# eae-pld-x.net
KiCad netlist of a schematic drawn in EAGLE
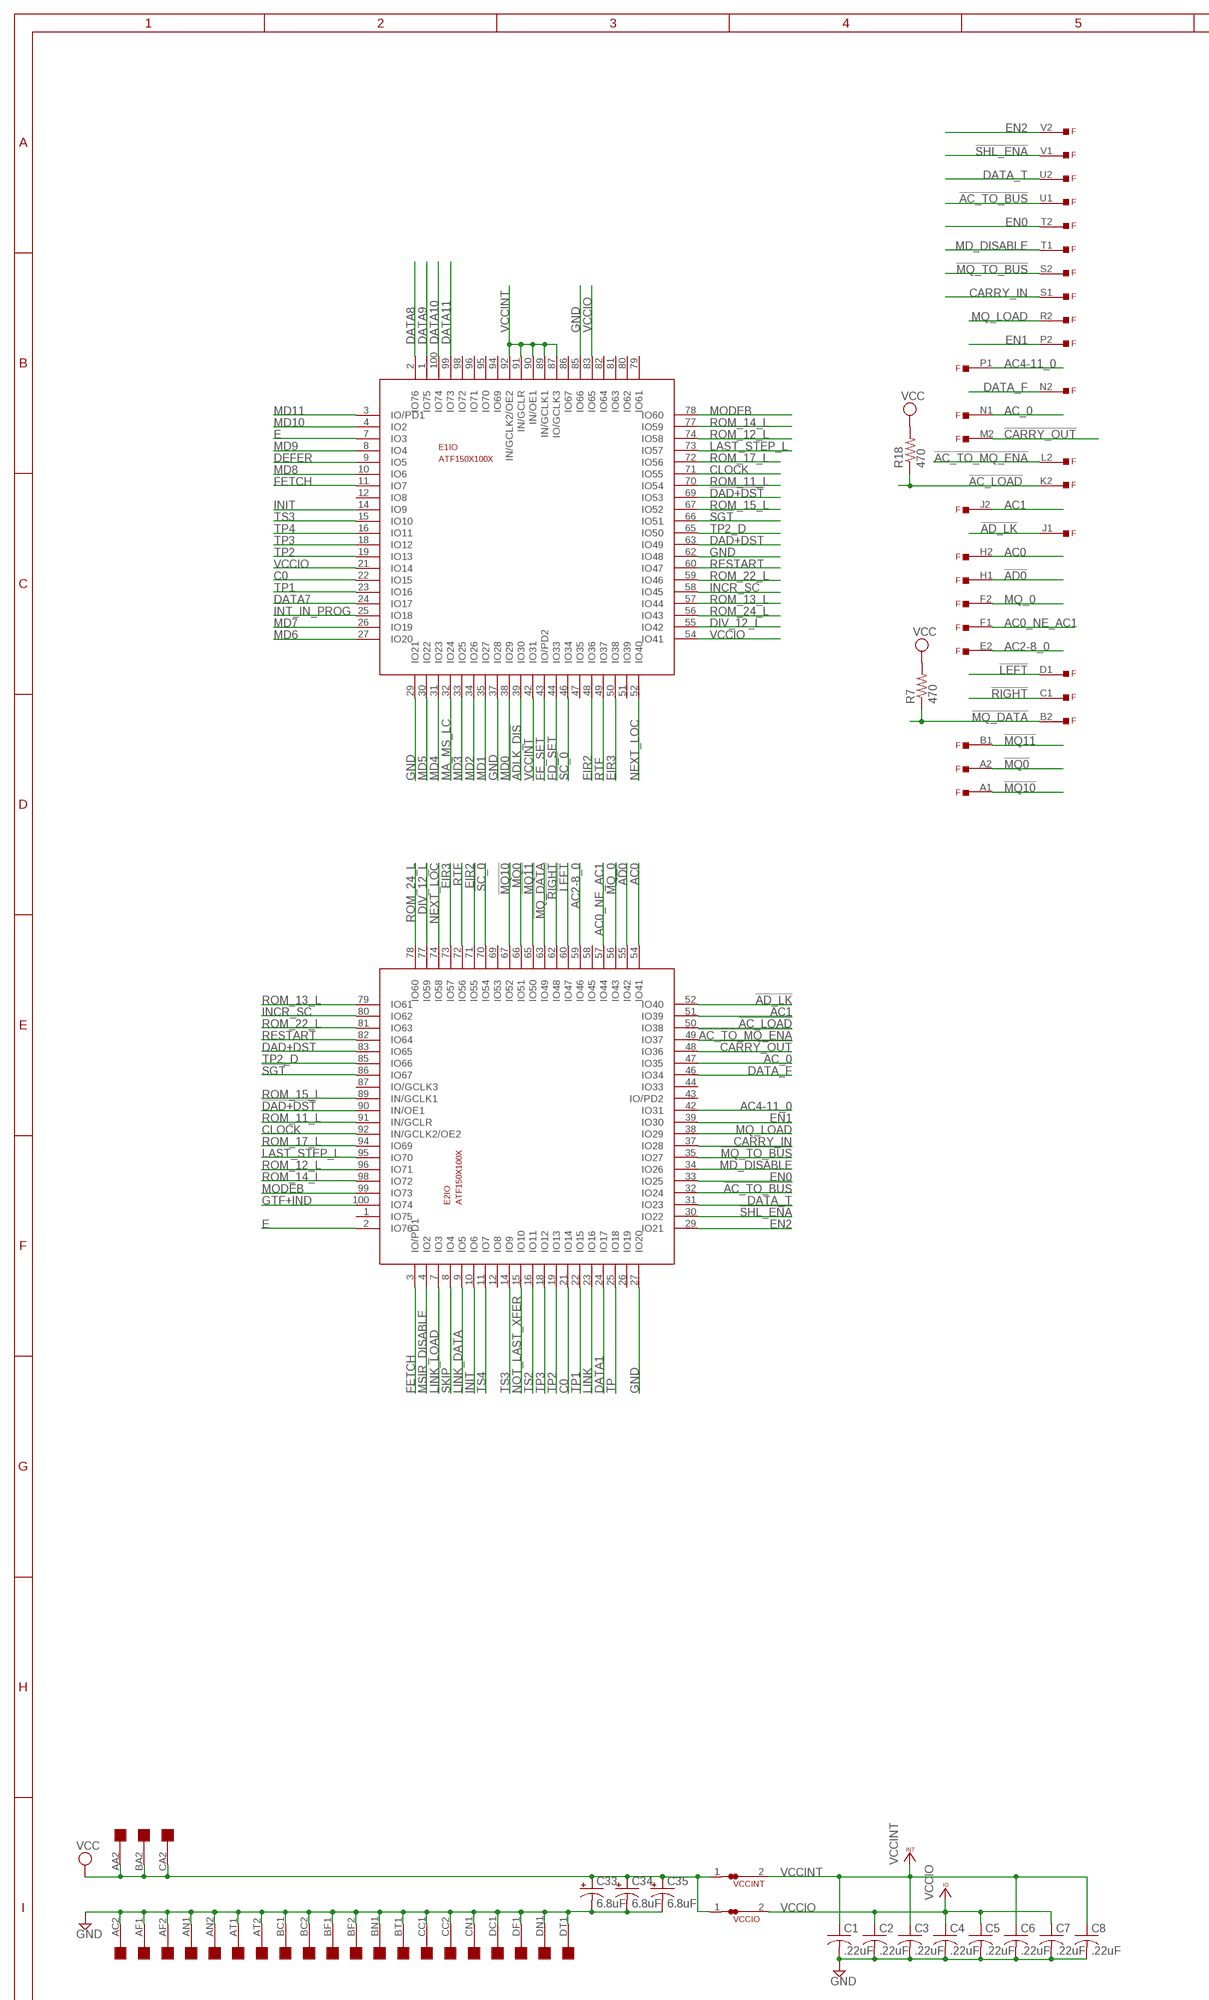
[diagram p0: schematic, sheet 1, part 1 of 2]
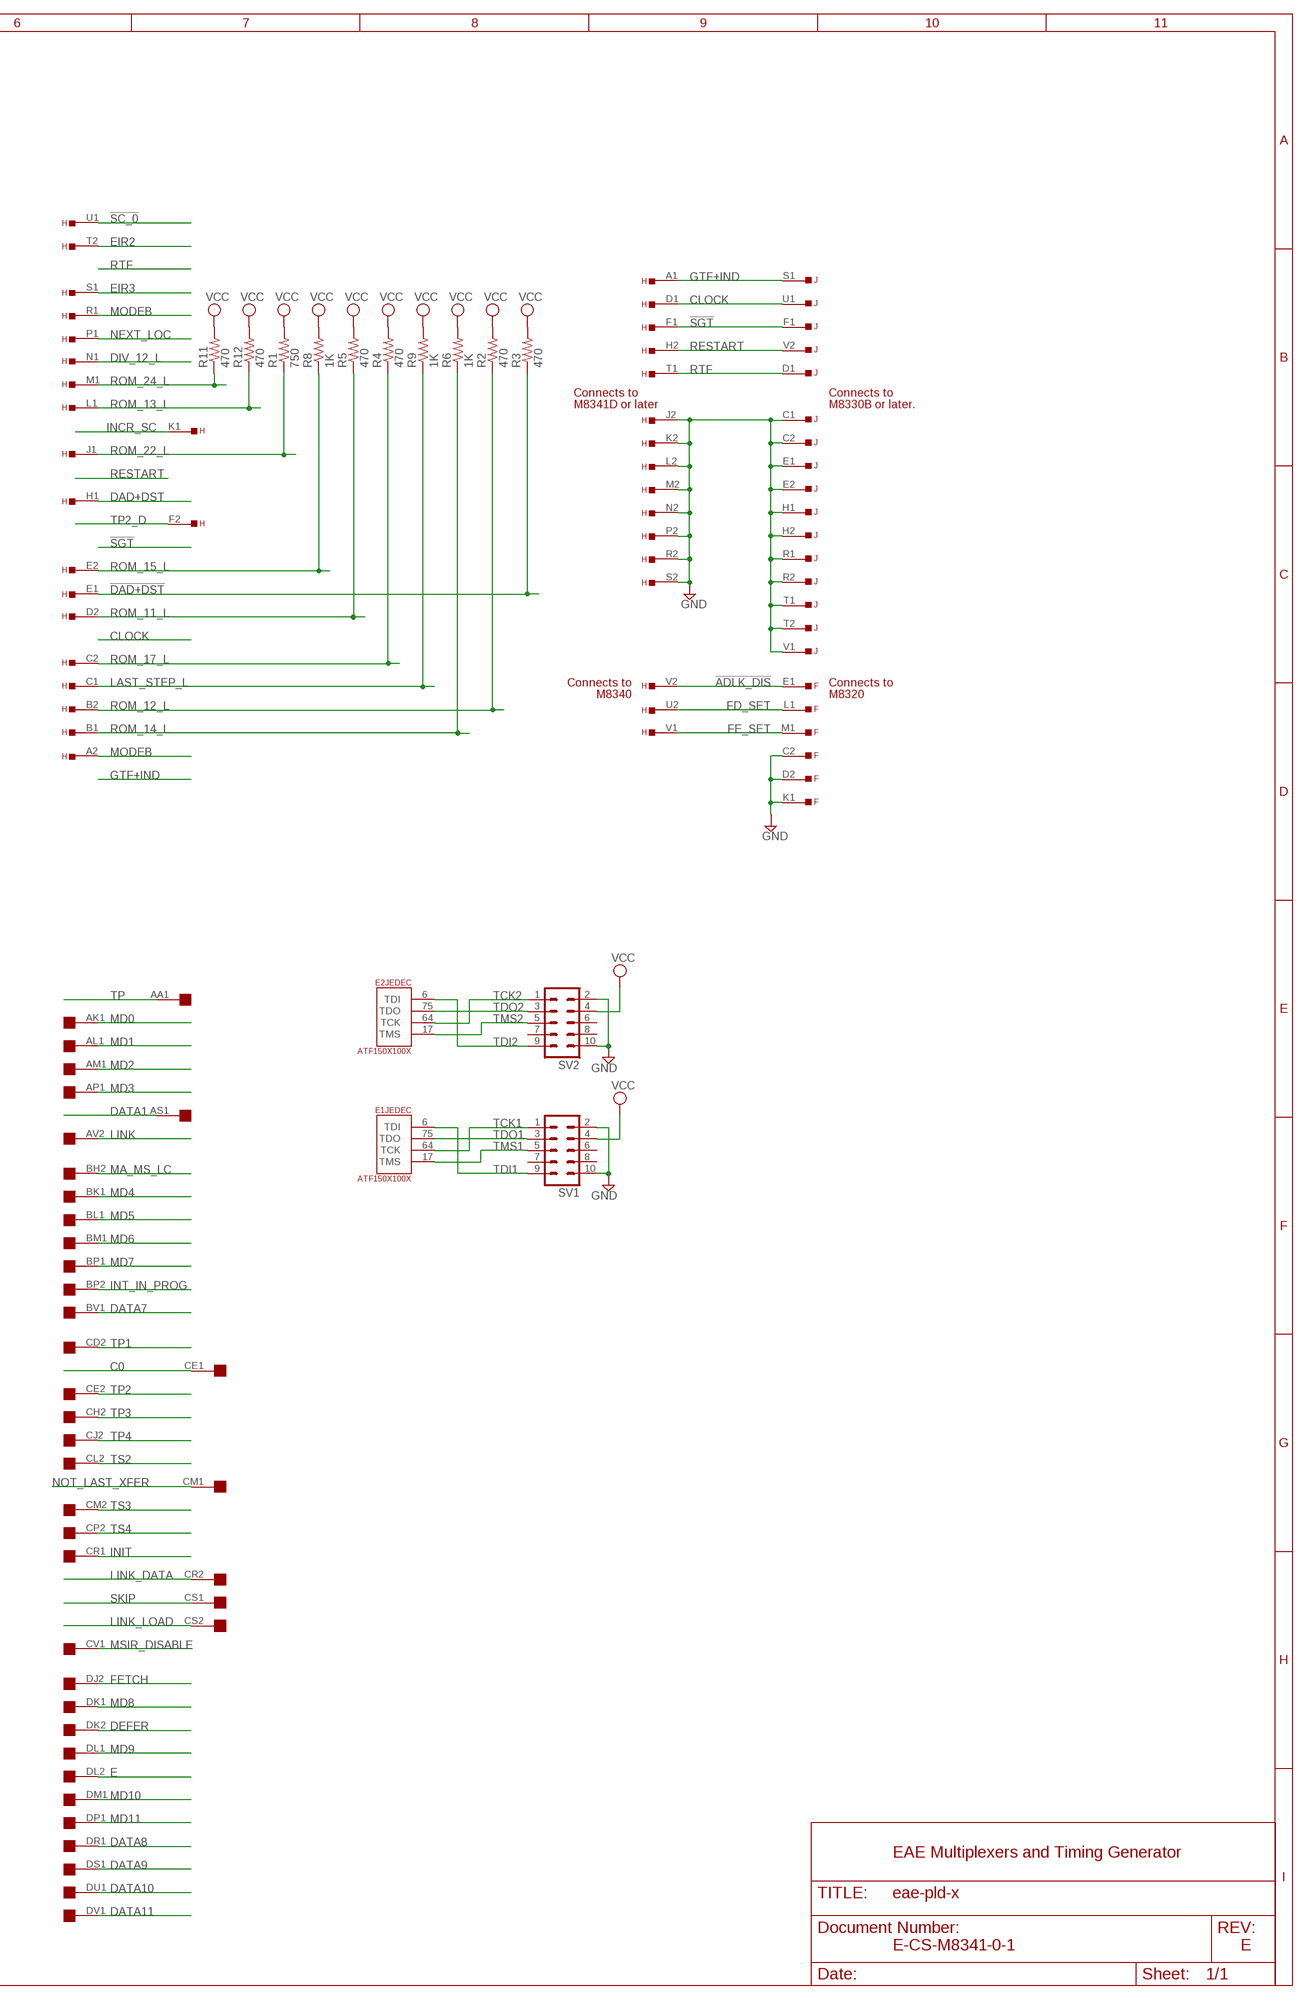
[diagram p1: schematic, sheet 1, part 2 of 2]

(export (version "E")
  (design (tool "Eeschema 10.0.6"))
  (components
    (comp (ref "C1")
      (value ".22uF")
      (footprint "eagle-import:C063-025X075")
      (libsource (lib "eagle-import") (part "C-US"))
    )
    (comp (ref "C2")
      (value ".22uF")
      (footprint "eagle-import:C063-025X075")
      (libsource (lib "eagle-import") (part "C-US"))
    )
    (comp (ref "C3")
      (value ".22uF")
      (footprint "eagle-import:C063-025X075")
      (libsource (lib "eagle-import") (part "C-US"))
    )
    (comp (ref "C4")
      (value ".22uF")
      (footprint "eagle-import:C063-025X075")
      (libsource (lib "eagle-import") (part "C-US"))
    )
    (comp (ref "C5")
      (value ".22uF")
      (footprint "eagle-import:C063-025X075")
      (libsource (lib "eagle-import") (part "C-US"))
    )
    (comp (ref "C6")
      (value ".22uF")
      (footprint "eagle-import:C063-025X075")
      (libsource (lib "eagle-import") (part "C-US"))
    )
    (comp (ref "C7")
      (value ".22uF")
      (footprint "eagle-import:C063-025X075")
      (libsource (lib "eagle-import") (part "C-US"))
    )
    (comp (ref "C8")
      (value ".22uF")
      (footprint "eagle-import:C063-025X075")
      (libsource (lib "eagle-import") (part "C-US"))
    )
    (comp (ref "C33")
      (value "6.8uF")
      (footprint "eagle-import:E12-8")
      (libsource (lib "eagle-import") (part "CPOL-USE20-8AXIAL"))
    )
    (comp (ref "C34")
      (value "6.8uF")
      (footprint "eagle-import:E12-8")
      (libsource (lib "eagle-import") (part "CPOL-USE20-8AXIAL"))
    )
    (comp (ref "C35")
      (value "6.8uF")
      (footprint "eagle-import:E12-8")
      (libsource (lib "eagle-import") (part "CPOL-USE20-8AXIAL"))
    )
    (comp (ref "E1")
      (value "ATF150X100X")
      (footprint "eagle-import:TH100B")
      (libsource (lib "eagle-import") (part "ATF150X100X"))
    )
    (comp (ref "E2")
      (value "ATF150X100X")
      (footprint "eagle-import:TH100B")
      (libsource (lib "eagle-import") (part "ATF150X100X"))
    )
    (comp (ref "F")
      (value "EDGE-TOP")
      (footprint "eagle-import:EDGE-CON2")
      (libsource (lib "eagle-import") (part "EDGE-TOP"))
    )
    (comp (ref "H")
      (value "EDGE-TOP")
      (footprint "eagle-import:EDGE-CON2")
      (libsource (lib "eagle-import") (part "EDGE-TOP"))
    )
    (comp (ref "J")
      (value "EDGE-TOP")
      (footprint "eagle-import:EDGE-CON2")
      (libsource (lib "eagle-import") (part "EDGE-TOP"))
    )
    (comp (ref "R1")
      (value "750")
      (footprint "eagle-import:0207_10")
      (libsource (lib "eagle-import") (part "R-US_0207/10"))
    )
    (comp (ref "R2")
      (value "470")
      (footprint "eagle-import:0207_10")
      (libsource (lib "eagle-import") (part "R-US_0207/10"))
    )
    (comp (ref "R3")
      (value "470")
      (footprint "eagle-import:0207_10")
      (libsource (lib "eagle-import") (part "R-US_0207/10"))
    )
    (comp (ref "R4")
      (value "470")
      (footprint "eagle-import:0207_10")
      (libsource (lib "eagle-import") (part "R-US_0207/10"))
    )
    (comp (ref "R5")
      (value "470")
      (footprint "eagle-import:0207_10")
      (libsource (lib "eagle-import") (part "R-US_0207/10"))
    )
    (comp (ref "R6")
      (value "1K")
      (footprint "eagle-import:0207_10")
      (libsource (lib "eagle-import") (part "R-US_0207/10"))
    )
    (comp (ref "R7")
      (value "470")
      (footprint "eagle-import:0207_10")
      (libsource (lib "eagle-import") (part "R-US_0207/10"))
    )
    (comp (ref "R8")
      (value "1K")
      (footprint "eagle-import:0207_10")
      (libsource (lib "eagle-import") (part "R-US_0207/10"))
    )
    (comp (ref "R9")
      (value "1K")
      (footprint "eagle-import:0207_10")
      (libsource (lib "eagle-import") (part "R-US_0207/10"))
    )
    (comp (ref "R11")
      (value "470")
      (footprint "eagle-import:0207_10")
      (libsource (lib "eagle-import") (part "R-US_0207/10"))
    )
    (comp (ref "R12")
      (value "470")
      (footprint "eagle-import:0207_10")
      (libsource (lib "eagle-import") (part "R-US_0207/10"))
    )
    (comp (ref "R18")
      (value "470")
      (footprint "eagle-import:0207_10")
      (libsource (lib "eagle-import") (part "R-US_0207/10"))
    )
    (comp (ref "SV1")
      (value "ML10")
      (footprint "eagle-import:ML10")
      (libsource (lib "eagle-import") (part "ML10"))
    )
    (comp (ref "SV2")
      (value "ML10")
      (footprint "eagle-import:ML10")
      (libsource (lib "eagle-import") (part "ML10"))
    )
    (comp (ref "U$1")
      (value "QUAD")
      (footprint "eagle-import:EDGE-CON8")
      (libsource (lib "eagle-import") (part "QUAD"))
    )
    (comp (ref "VCCINT")
      (value "JUMPER-NC1")
      (footprint "eagle-import:NC1")
      (libsource (lib "eagle-import") (part "JUMPER-NC1"))
    )
    (comp (ref "VCCIO")
      (value "JUMPER-NC1")
      (footprint "eagle-import:NC1")
      (libsource (lib "eagle-import") (part "JUMPER-NC1"))
    )
  )
  (nets
    (net (code "1") (name "/AC0") (class "Default")
      (node (ref "E2") (pin "54") (pinfunction "IO41_54") (pintype "bidirectional"))
      (node (ref "F") (pin "H2") (pinfunction "P_H2") (pintype "passive"))
    )
    (net (code "2") (name "/AC0_NE_AC1") (class "Default")
      (node (ref "E2") (pin "57") (pinfunction "IO44_57") (pintype "bidirectional"))
      (node (ref "F") (pin "F1") (pinfunction "P_F1") (pintype "passive"))
    )
    (net (code "3") (name "/AC1") (class "Default")
      (node (ref "E2") (pin "51") (pinfunction "IO39_51") (pintype "bidirectional"))
      (node (ref "F") (pin "J2") (pinfunction "P_J2") (pintype "passive"))
    )
    (net (code "4") (name "/AC2-8_0") (class "Default")
      (node (ref "E2") (pin "59") (pinfunction "IO46_59") (pintype "bidirectional"))
      (node (ref "F") (pin "E2") (pinfunction "P_E2") (pintype "passive"))
    )
    (net (code "5") (name "/AC4-11_0") (class "Default")
      (node (ref "E2") (pin "42") (pinfunction "IO31_42") (pintype "bidirectional"))
      (node (ref "F") (pin "P1") (pinfunction "P_P1") (pintype "passive"))
    )
    (net (code "6") (name "/AC_0") (class "Default")
      (node (ref "E2") (pin "47") (pinfunction "IO35_47") (pintype "bidirectional"))
      (node (ref "F") (pin "N1") (pinfunction "P_N1") (pintype "passive"))
    )
    (net (code "7") (name "/C0") (class "Default")
      (node (ref "E1") (pin "22") (pinfunction "IO15_22") (pintype "bidirectional"))
      (node (ref "E2") (pin "21") (pinfunction "IO14_21") (pintype "bidirectional"))
      (node (ref "U$1") (pin "CE1") (pinfunction "1_CE1") (pintype "bidirectional"))
    )
    (net (code "8") (name "/CARRY_IN") (class "Default")
      (node (ref "E2") (pin "37") (pinfunction "IO28_37") (pintype "bidirectional"))
      (node (ref "F") (pin "S1") (pinfunction "P_S1") (pintype "passive"))
    )
    (net (code "9") (name "/CLOCK") (class "Default")
      (node (ref "E1") (pin "71") (pinfunction "IO55_71") (pintype "bidirectional"))
      (node (ref "E2") (pin "92") (pinfunction "IN/GCLK2/OE2_92") (pintype "input"))
      (node (ref "H") (pin "D1") (pinfunction "P_D1") (pintype "passive"))
      (node (ref "J") (pin "U1") (pinfunction "P_U1") (pintype "passive"))
    )
    (net (code "10") (name "/DAD+DST") (class "Default")
      (node (ref "E1") (pin "63") (pinfunction "IO49_63") (pintype "bidirectional"))
      (node (ref "E2") (pin "83") (pinfunction "IO65_83") (pintype "bidirectional"))
      (node (ref "H") (pin "H1") (pinfunction "P_H1") (pintype "passive"))
    )
    (net (code "11") (name "/DATA1") (class "Default")
      (node (ref "E2") (pin "24") (pinfunction "IO17_24") (pintype "bidirectional"))
      (node (ref "U$1") (pin "AS1") (pinfunction "1_AS1") (pintype "bidirectional"))
    )
    (net (code "12") (name "/DATA7") (class "Default")
      (node (ref "E1") (pin "24") (pinfunction "IO17_24") (pintype "bidirectional"))
      (node (ref "U$1") (pin "BV1") (pinfunction "1_BV1") (pintype "bidirectional"))
    )
    (net (code "13") (name "/DATA8") (class "Default")
      (node (ref "E1") (pin "2") (pinfunction "IO76_2") (pintype "bidirectional"))
      (node (ref "U$1") (pin "DR1") (pinfunction "1_DR1") (pintype "bidirectional"))
    )
    (net (code "14") (name "/DATA9") (class "Default")
      (node (ref "E1") (pin "1") (pinfunction "IO75_1") (pintype "bidirectional"))
      (node (ref "U$1") (pin "DS1") (pinfunction "1_DS1") (pintype "bidirectional"))
    )
    (net (code "15") (name "/DATA10") (class "Default")
      (node (ref "E1") (pin "100") (pinfunction "IO74_100") (pintype "bidirectional"))
      (node (ref "U$1") (pin "DU1") (pinfunction "1_DU1") (pintype "bidirectional"))
    )
    (net (code "16") (name "/DATA11") (class "Default")
      (node (ref "E1") (pin "99") (pinfunction "IO73_99") (pintype "bidirectional"))
      (node (ref "U$1") (pin "DV1") (pinfunction "1_DV1") (pintype "bidirectional"))
    )
    (net (code "17") (name "/DATA_F") (class "Default")
      (node (ref "E2") (pin "46") (pinfunction "IO34_46") (pintype "bidirectional"))
      (node (ref "F") (pin "N2") (pinfunction "P_N2") (pintype "passive"))
    )
    (net (code "18") (name "/DATA_T") (class "Default")
      (node (ref "E2") (pin "31") (pinfunction "IO23_31") (pintype "bidirectional"))
      (node (ref "F") (pin "U2") (pinfunction "P_U2") (pintype "passive"))
    )
    (net (code "19") (name "/DEFER") (class "Default")
      (node (ref "E1") (pin "9") (pinfunction "IO5_9") (pintype "bidirectional"))
      (node (ref "U$1") (pin "DK2") (pinfunction "1_DK2") (pintype "bidirectional"))
    )
    (net (code "20") (name "/DIV_12_L") (class "Default")
      (node (ref "E1") (pin "55") (pinfunction "IO42_55") (pintype "bidirectional"))
      (node (ref "E2") (pin "77") (pinfunction "IO59_77") (pintype "bidirectional"))
      (node (ref "H") (pin "N1") (pinfunction "P_N1") (pintype "passive"))
    )
    (net (code "21") (name "/E") (class "Default")
      (node (ref "E1") (pin "7") (pinfunction "IO3_7") (pintype "bidirectional"))
      (node (ref "E2") (pin "2") (pinfunction "IO76_2") (pintype "bidirectional"))
      (node (ref "U$1") (pin "DL2") (pinfunction "1_DL2") (pintype "bidirectional"))
    )
    (net (code "22") (name "/EIR2") (class "Default")
      (node (ref "E1") (pin "48") (pinfunction "IO36_48") (pintype "bidirectional"))
      (node (ref "E2") (pin "71") (pinfunction "IO55_71") (pintype "bidirectional"))
      (node (ref "H") (pin "T2") (pinfunction "P_T2") (pintype "passive"))
    )
    (net (code "23") (name "/EIR3") (class "Default")
      (node (ref "E1") (pin "50") (pinfunction "IO38_50") (pintype "bidirectional"))
      (node (ref "E2") (pin "73") (pinfunction "IO57_73") (pintype "bidirectional"))
      (node (ref "H") (pin "S1") (pinfunction "P_S1") (pintype "passive"))
    )
    (net (code "24") (name "/EN0") (class "Default")
      (node (ref "E2") (pin "33") (pinfunction "IO25_33") (pintype "bidirectional"))
      (node (ref "F") (pin "T2") (pinfunction "P_T2") (pintype "passive"))
    )
    (net (code "25") (name "/EN1") (class "Default")
      (node (ref "E2") (pin "39") (pinfunction "IO30_39") (pintype "bidirectional"))
      (node (ref "F") (pin "P2") (pinfunction "P_P2") (pintype "passive"))
    )
    (net (code "26") (name "/EN2") (class "Default")
      (node (ref "E2") (pin "29") (pinfunction "IO21_29") (pintype "bidirectional"))
      (node (ref "F") (pin "V2") (pinfunction "P_V2") (pintype "passive"))
    )
    (net (code "27") (name "/FD_SET") (class "Default")
      (node (ref "E1") (pin "44") (pinfunction "IO33_44") (pintype "bidirectional"))
      (node (ref "F") (pin "L1") (pinfunction "P_L1") (pintype "passive"))
      (node (ref "H") (pin "U2") (pinfunction "P_U2") (pintype "passive"))
    )
    (net (code "28") (name "/FETCH") (class "Default")
      (node (ref "E1") (pin "11") (pinfunction "IO7_11") (pintype "bidirectional"))
      (node (ref "E2") (pin "3") (pinfunction "IO/PD1_3") (pintype "bidirectional"))
      (node (ref "U$1") (pin "DJ2") (pinfunction "1_DJ2") (pintype "bidirectional"))
    )
    (net (code "29") (name "/FE_SET") (class "Default")
      (node (ref "E1") (pin "43") (pinfunction "IO/PD2_43") (pintype "bidirectional"))
      (node (ref "F") (pin "M1") (pinfunction "P_M1") (pintype "passive"))
      (node (ref "H") (pin "V1") (pinfunction "P_V1") (pintype "passive"))
    )
    (net (code "30") (name "/GTF+IND") (class "Default")
      (node (ref "E2") (pin "100") (pinfunction "IO74_100") (pintype "bidirectional"))
      (node (ref "H") (pin "A1") (pinfunction "P_A1") (pintype "passive"))
      (node (ref "J") (pin "S1") (pinfunction "P_S1") (pintype "passive"))
    )
    (net (code "31") (name "/INCR_SC") (class "Default")
      (node (ref "E1") (pin "58") (pinfunction "IO45_58") (pintype "bidirectional"))
      (node (ref "E2") (pin "80") (pinfunction "IO62_80") (pintype "bidirectional"))
      (node (ref "H") (pin "K1") (pinfunction "P_K1") (pintype "passive"))
    )
    (net (code "32") (name "/INIT") (class "Default")
      (node (ref "E1") (pin "14") (pinfunction "IO9_14") (pintype "bidirectional"))
      (node (ref "E2") (pin "10") (pinfunction "IO6_10") (pintype "bidirectional"))
      (node (ref "U$1") (pin "CR1") (pinfunction "1_CR1") (pintype "bidirectional"))
    )
    (net (code "33") (name "/INT_IN_PROG") (class "Default")
      (node (ref "E1") (pin "25") (pinfunction "IO18_25") (pintype "bidirectional"))
      (node (ref "U$1") (pin "BP2") (pinfunction "1_BP2") (pintype "bidirectional"))
    )
    (net (code "34") (name "/LAST_STEP_L") (class "Default")
      (node (ref "E1") (pin "73") (pinfunction "IO57_73") (pintype "bidirectional"))
      (node (ref "E2") (pin "95") (pinfunction "IO70_95") (pintype "bidirectional"))
      (node (ref "H") (pin "C1") (pinfunction "P_C1") (pintype "passive"))
      (node (ref "R9") (pin "1") (pinfunction "1_1") (pintype "passive"))
    )
    (net (code "35") (name "/LINK") (class "Default")
      (node (ref "E2") (pin "23") (pinfunction "IO16_23") (pintype "bidirectional"))
      (node (ref "U$1") (pin "AV2") (pinfunction "1_AV2") (pintype "bidirectional"))
    )
    (net (code "36") (name "/LINK_DATA") (class "Default")
      (node (ref "E2") (pin "9") (pinfunction "IO5_9") (pintype "bidirectional"))
      (node (ref "U$1") (pin "CR2") (pinfunction "1_CR2") (pintype "bidirectional"))
    )
    (net (code "37") (name "/LINK_LOAD") (class "Default")
      (node (ref "E2") (pin "7") (pinfunction "IO3_7") (pintype "bidirectional"))
      (node (ref "U$1") (pin "CS2") (pinfunction "1_CS2") (pintype "bidirectional"))
    )
    (net (code "38") (name "/MA_MS_LC") (class "Default")
      (node (ref "E1") (pin "32") (pinfunction "IO24_32") (pintype "bidirectional"))
      (node (ref "U$1") (pin "BH2") (pinfunction "1_BH2") (pintype "bidirectional"))
    )
    (net (code "39") (name "/MD0") (class "Default")
      (node (ref "E1") (pin "38") (pinfunction "IO29_38") (pintype "bidirectional"))
      (node (ref "U$1") (pin "AK1") (pinfunction "1_AK1") (pintype "bidirectional"))
    )
    (net (code "40") (name "/MD1") (class "Default")
      (node (ref "E1") (pin "35") (pinfunction "IO27_35") (pintype "bidirectional"))
      (node (ref "U$1") (pin "AL1") (pinfunction "1_AL1") (pintype "bidirectional"))
    )
    (net (code "41") (name "/MD2") (class "Default")
      (node (ref "E1") (pin "34") (pinfunction "IO26_34") (pintype "bidirectional"))
      (node (ref "U$1") (pin "AM1") (pinfunction "1_AM1") (pintype "bidirectional"))
    )
    (net (code "42") (name "/MD3") (class "Default")
      (node (ref "E1") (pin "33") (pinfunction "IO25_33") (pintype "bidirectional"))
      (node (ref "U$1") (pin "AP1") (pinfunction "1_AP1") (pintype "bidirectional"))
    )
    (net (code "43") (name "/MD4") (class "Default")
      (node (ref "E1") (pin "31") (pinfunction "IO23_31") (pintype "bidirectional"))
      (node (ref "U$1") (pin "BK1") (pinfunction "1_BK1") (pintype "bidirectional"))
    )
    (net (code "44") (name "/MD5") (class "Default")
      (node (ref "E1") (pin "30") (pinfunction "IO22_30") (pintype "bidirectional"))
      (node (ref "U$1") (pin "BL1") (pinfunction "1_BL1") (pintype "bidirectional"))
    )
    (net (code "45") (name "/MD6") (class "Default")
      (node (ref "E1") (pin "27") (pinfunction "IO20_27") (pintype "bidirectional"))
      (node (ref "U$1") (pin "BM1") (pinfunction "1_BM1") (pintype "bidirectional"))
    )
    (net (code "46") (name "/MD7") (class "Default")
      (node (ref "E1") (pin "26") (pinfunction "IO19_26") (pintype "bidirectional"))
      (node (ref "U$1") (pin "BP1") (pinfunction "1_BP1") (pintype "bidirectional"))
    )
    (net (code "47") (name "/MD8") (class "Default")
      (node (ref "E1") (pin "10") (pinfunction "IO6_10") (pintype "bidirectional"))
      (node (ref "U$1") (pin "DK1") (pinfunction "1_DK1") (pintype "bidirectional"))
    )
    (net (code "48") (name "/MD9") (class "Default")
      (node (ref "E1") (pin "8") (pinfunction "IO4_8") (pintype "bidirectional"))
      (node (ref "U$1") (pin "DL1") (pinfunction "1_DL1") (pintype "bidirectional"))
    )
    (net (code "49") (name "/MD10") (class "Default")
      (node (ref "E1") (pin "4") (pinfunction "IO2_4") (pintype "bidirectional"))
      (node (ref "U$1") (pin "DM1") (pinfunction "1_DM1") (pintype "bidirectional"))
    )
    (net (code "50") (name "/MD11") (class "Default")
      (node (ref "E1") (pin "3") (pinfunction "IO/PD1_3") (pintype "bidirectional"))
      (node (ref "U$1") (pin "DP1") (pinfunction "1_DP1") (pintype "bidirectional"))
    )
    (net (code "51") (name "/MD_DISABLE") (class "Default")
      (node (ref "E2") (pin "34") (pinfunction "IO26_34") (pintype "bidirectional"))
      (node (ref "F") (pin "T1") (pinfunction "P_T1") (pintype "passive"))
    )
    (net (code "52") (name "/MODEB") (class "Default")
      (node (ref "E1") (pin "78") (pinfunction "IO60_78") (pintype "bidirectional"))
      (node (ref "E2") (pin "99") (pinfunction "IO73_99") (pintype "bidirectional"))
      (node (ref "H") (pin "A2") (pinfunction "P_A2") (pintype "passive"))
      (node (ref "H") (pin "R1") (pinfunction "P_R1") (pintype "passive"))
    )
    (net (code "53") (name "/MQ_0") (class "Default")
      (node (ref "E2") (pin "56") (pinfunction "IO43_56") (pintype "bidirectional"))
      (node (ref "F") (pin "F2") (pinfunction "P_F2") (pintype "passive"))
    )
    (net (code "54") (name "/MQ_LOAD") (class "Default")
      (node (ref "E2") (pin "38") (pinfunction "IO29_38") (pintype "bidirectional"))
      (node (ref "F") (pin "R2") (pinfunction "P_R2") (pintype "passive"))
    )
    (net (code "55") (name "/MSIR_DISABLE") (class "Default")
      (node (ref "E2") (pin "4") (pinfunction "IO2_4") (pintype "bidirectional"))
      (node (ref "U$1") (pin "CV1") (pinfunction "1_CV1") (pintype "bidirectional"))
    )
    (net (code "56") (name "/NEXT_LOC") (class "Default")
      (node (ref "E1") (pin "52") (pinfunction "IO40_52") (pintype "bidirectional"))
      (node (ref "E2") (pin "74") (pinfunction "IO58_74") (pintype "bidirectional"))
      (node (ref "H") (pin "P1") (pinfunction "P_P1") (pintype "passive"))
    )
    (net (code "57") (name "/NOT_LAST_XFER") (class "Default")
      (node (ref "E2") (pin "15") (pinfunction "IO10_15") (pintype "bidirectional"))
      (node (ref "U$1") (pin "CM1") (pinfunction "1_CM1") (pintype "bidirectional"))
    )
    (net (code "58") (name "/RESTART") (class "Default")
      (node (ref "E1") (pin "60") (pinfunction "IO47_60") (pintype "bidirectional"))
      (node (ref "E2") (pin "82") (pinfunction "IO64_82") (pintype "bidirectional"))
      (node (ref "H") (pin "H2") (pinfunction "P_H2") (pintype "passive"))
      (node (ref "J") (pin "V2") (pinfunction "P_V2") (pintype "passive"))
    )
    (net (code "59") (name "/ROM_11_L") (class "Default")
      (node (ref "E1") (pin "70") (pinfunction "IO54_70") (pintype "bidirectional"))
      (node (ref "E2") (pin "91") (pinfunction "IN/GCLR_91") (pintype "input"))
      (node (ref "H") (pin "D2") (pinfunction "P_D2") (pintype "passive"))
      (node (ref "R5") (pin "1") (pinfunction "1_1") (pintype "passive"))
    )
    (net (code "60") (name "/ROM_12_L") (class "Default")
      (node (ref "E1") (pin "74") (pinfunction "IO58_74") (pintype "bidirectional"))
      (node (ref "E2") (pin "96") (pinfunction "IO71_96") (pintype "bidirectional"))
      (node (ref "H") (pin "B2") (pinfunction "P_B2") (pintype "passive"))
      (node (ref "R2") (pin "1") (pinfunction "1_1") (pintype "passive"))
    )
    (net (code "61") (name "/ROM_13_L") (class "Default")
      (node (ref "E1") (pin "57") (pinfunction "IO44_57") (pintype "bidirectional"))
      (node (ref "E2") (pin "79") (pinfunction "IO61_79") (pintype "bidirectional"))
      (node (ref "H") (pin "L1") (pinfunction "P_L1") (pintype "passive"))
      (node (ref "R12") (pin "1") (pinfunction "1_1") (pintype "passive"))
    )
    (net (code "62") (name "/ROM_14_L") (class "Default")
      (node (ref "E1") (pin "77") (pinfunction "IO59_77") (pintype "bidirectional"))
      (node (ref "E2") (pin "98") (pinfunction "IO72_98") (pintype "bidirectional"))
      (node (ref "H") (pin "B1") (pinfunction "P_B1") (pintype "passive"))
      (node (ref "R6") (pin "1") (pinfunction "1_1") (pintype "passive"))
    )
    (net (code "63") (name "/ROM_15_L") (class "Default")
      (node (ref "E1") (pin "67") (pinfunction "IO52_67") (pintype "bidirectional"))
      (node (ref "E2") (pin "89") (pinfunction "IN/GCLK1_89") (pintype "input"))
      (node (ref "H") (pin "E2") (pinfunction "P_E2") (pintype "passive"))
      (node (ref "R8") (pin "1") (pinfunction "1_1") (pintype "passive"))
    )
    (net (code "64") (name "/ROM_17_L") (class "Default")
      (node (ref "E1") (pin "72") (pinfunction "IO56_72") (pintype "bidirectional"))
      (node (ref "E2") (pin "94") (pinfunction "IO69_94") (pintype "bidirectional"))
      (node (ref "H") (pin "C2") (pinfunction "P_C2") (pintype "passive"))
      (node (ref "R4") (pin "1") (pinfunction "1_1") (pintype "passive"))
    )
    (net (code "65") (name "/ROM_22_L") (class "Default")
      (node (ref "E1") (pin "59") (pinfunction "IO46_59") (pintype "bidirectional"))
      (node (ref "E2") (pin "81") (pinfunction "IO63_81") (pintype "bidirectional"))
      (node (ref "H") (pin "J1") (pinfunction "P_J1") (pintype "passive"))
      (node (ref "R1") (pin "1") (pinfunction "1_1") (pintype "passive"))
    )
    (net (code "66") (name "/ROM_24_L") (class "Default")
      (node (ref "E1") (pin "56") (pinfunction "IO43_56") (pintype "bidirectional"))
      (node (ref "E2") (pin "78") (pinfunction "IO60_78") (pintype "bidirectional"))
      (node (ref "H") (pin "M1") (pinfunction "P_M1") (pintype "passive"))
      (node (ref "R11") (pin "1") (pinfunction "1_1") (pintype "passive"))
    )
    (net (code "67") (name "/RTF") (class "Default")
      (node (ref "E1") (pin "49") (pinfunction "IO37_49") (pintype "bidirectional"))
      (node (ref "E2") (pin "72") (pinfunction "IO56_72") (pintype "bidirectional"))
      (node (ref "H") (pin "T1") (pinfunction "P_T1") (pintype "passive"))
      (node (ref "J") (pin "D1") (pinfunction "P_D1") (pintype "passive"))
    )
    (net (code "68") (name "/SKIP") (class "Default")
      (node (ref "E2") (pin "8") (pinfunction "IO4_8") (pintype "bidirectional"))
      (node (ref "U$1") (pin "CS1") (pinfunction "1_CS1") (pintype "bidirectional"))
    )
    (net (code "69") (name "/TCK1") (class "Default")
      (node (ref "E1") (pin "64") (pinfunction "TCK_64") (pintype "bidirectional"))
      (node (ref "SV1") (pin "1") (pinfunction "1_1") (pintype "passive"))
    )
    (net (code "70") (name "/TCK2") (class "Default")
      (node (ref "E2") (pin "64") (pinfunction "TCK_64") (pintype "bidirectional"))
      (node (ref "SV2") (pin "1") (pinfunction "1_1") (pintype "passive"))
    )
    (net (code "71") (name "/TDI1") (class "Default")
      (node (ref "E1") (pin "6") (pinfunction "TDI_6") (pintype "bidirectional"))
      (node (ref "SV1") (pin "9") (pinfunction "9_9") (pintype "passive"))
    )
    (net (code "72") (name "/TDI2") (class "Default")
      (node (ref "E2") (pin "6") (pinfunction "TDI_6") (pintype "bidirectional"))
      (node (ref "SV2") (pin "9") (pinfunction "9_9") (pintype "passive"))
    )
    (net (code "73") (name "/TDO1") (class "Default")
      (node (ref "E1") (pin "75") (pinfunction "TDO_75") (pintype "bidirectional"))
      (node (ref "SV1") (pin "3") (pinfunction "3_3") (pintype "passive"))
    )
    (net (code "74") (name "/TDO2") (class "Default")
      (node (ref "E2") (pin "75") (pinfunction "TDO_75") (pintype "bidirectional"))
      (node (ref "SV2") (pin "3") (pinfunction "3_3") (pintype "passive"))
    )
    (net (code "75") (name "/TMS1") (class "Default")
      (node (ref "E1") (pin "17") (pinfunction "TMS_17") (pintype "bidirectional"))
      (node (ref "SV1") (pin "5") (pinfunction "5_5") (pintype "passive"))
    )
    (net (code "76") (name "/TMS2") (class "Default")
      (node (ref "E2") (pin "17") (pinfunction "TMS_17") (pintype "bidirectional"))
      (node (ref "SV2") (pin "5") (pinfunction "5_5") (pintype "passive"))
    )
    (net (code "77") (name "/TP") (class "Default")
      (node (ref "E2") (pin "25") (pinfunction "IO18_25") (pintype "bidirectional"))
      (node (ref "U$1") (pin "AA1") (pinfunction "1_AA1") (pintype "bidirectional"))
    )
    (net (code "78") (name "/TP1") (class "Default")
      (node (ref "E1") (pin "23") (pinfunction "IO16_23") (pintype "bidirectional"))
      (node (ref "E2") (pin "22") (pinfunction "IO15_22") (pintype "bidirectional"))
      (node (ref "U$1") (pin "CD2") (pinfunction "1_CD2") (pintype "bidirectional"))
    )
    (net (code "79") (name "/TP2") (class "Default")
      (node (ref "E1") (pin "19") (pinfunction "IO13_19") (pintype "bidirectional"))
      (node (ref "E2") (pin "19") (pinfunction "IO13_19") (pintype "bidirectional"))
      (node (ref "U$1") (pin "CE2") (pinfunction "1_CE2") (pintype "bidirectional"))
    )
    (net (code "80") (name "/TP2_D") (class "Default")
      (node (ref "E1") (pin "65") (pinfunction "IO50_65") (pintype "bidirectional"))
      (node (ref "E2") (pin "85") (pinfunction "IO66_85") (pintype "bidirectional"))
      (node (ref "H") (pin "F2") (pinfunction "P_F2") (pintype "passive"))
    )
    (net (code "81") (name "/TP3") (class "Default")
      (node (ref "E1") (pin "18") (pinfunction "IO12_18") (pintype "bidirectional"))
      (node (ref "E2") (pin "18") (pinfunction "IO12_18") (pintype "bidirectional"))
      (node (ref "U$1") (pin "CH2") (pinfunction "1_CH2") (pintype "bidirectional"))
    )
    (net (code "82") (name "/TP4") (class "Default")
      (node (ref "E1") (pin "16") (pinfunction "IO11_16") (pintype "bidirectional"))
      (node (ref "U$1") (pin "CJ2") (pinfunction "1_CJ2") (pintype "bidirectional"))
    )
    (net (code "83") (name "/TS2") (class "Default")
      (node (ref "E2") (pin "16") (pinfunction "IO11_16") (pintype "bidirectional"))
      (node (ref "U$1") (pin "CL2") (pinfunction "1_CL2") (pintype "bidirectional"))
    )
    (net (code "84") (name "/TS3") (class "Default")
      (node (ref "E1") (pin "15") (pinfunction "IO10_15") (pintype "bidirectional"))
      (node (ref "E2") (pin "14") (pinfunction "IO9_14") (pintype "bidirectional"))
      (node (ref "U$1") (pin "CM2") (pinfunction "1_CM2") (pintype "bidirectional"))
    )
    (net (code "85") (name "/TS4") (class "Default")
      (node (ref "E2") (pin "11") (pinfunction "IO7_11") (pintype "bidirectional"))
      (node (ref "U$1") (pin "CP2") (pinfunction "1_CP2") (pintype "bidirectional"))
    )
    (net (code "86") (name "/~{AC_LOAD}") (class "Default")
      (node (ref "E2") (pin "50") (pinfunction "IO38_50") (pintype "bidirectional"))
      (node (ref "F") (pin "K2") (pinfunction "P_K2") (pintype "passive"))
      (node (ref "R18") (pin "1") (pinfunction "1_1") (pintype "passive"))
    )
    (net (code "87") (name "/~{AC_TO_BUS}") (class "Default")
      (node (ref "E2") (pin "32") (pinfunction "IO24_32") (pintype "bidirectional"))
      (node (ref "F") (pin "U1") (pinfunction "P_U1") (pintype "passive"))
    )
    (net (code "88") (name "/~{AC_TO_MQ_ENA}") (class "Default")
      (node (ref "E2") (pin "49") (pinfunction "IO37_49") (pintype "bidirectional"))
      (node (ref "F") (pin "L2") (pinfunction "P_L2") (pintype "passive"))
    )
    (net (code "89") (name "/~{AD0}") (class "Default")
      (node (ref "E2") (pin "55") (pinfunction "IO42_55") (pintype "bidirectional"))
      (node (ref "F") (pin "H1") (pinfunction "P_H1") (pintype "passive"))
    )
    (net (code "90") (name "/~{ADLK_DIS}") (class "Default")
      (node (ref "E1") (pin "39") (pinfunction "IO30_39") (pintype "bidirectional"))
      (node (ref "F") (pin "E1") (pinfunction "P_E1") (pintype "passive"))
      (node (ref "H") (pin "V2") (pinfunction "P_V2") (pintype "passive"))
    )
    (net (code "91") (name "/~{AD_LK}") (class "Default")
      (node (ref "E2") (pin "52") (pinfunction "IO40_52") (pintype "bidirectional"))
      (node (ref "F") (pin "J1") (pinfunction "P_J1") (pintype "passive"))
    )
    (net (code "92") (name "/~{CARRY_OUT}") (class "Default")
      (node (ref "E2") (pin "48") (pinfunction "IO36_48") (pintype "bidirectional"))
      (node (ref "F") (pin "M2") (pinfunction "P_M2") (pintype "passive"))
    )
    (net (code "93") (name "/~{DAD+DST}") (class "Default")
      (node (ref "E1") (pin "69") (pinfunction "IO53_69") (pintype "bidirectional"))
      (node (ref "E2") (pin "90") (pinfunction "IN/OE1_90") (pintype "input"))
      (node (ref "H") (pin "E1") (pinfunction "P_E1") (pintype "passive"))
      (node (ref "R3") (pin "1") (pinfunction "1_1") (pintype "passive"))
    )
    (net (code "94") (name "/~{LEFT}") (class "Default")
      (node (ref "E2") (pin "60") (pinfunction "IO47_60") (pintype "bidirectional"))
      (node (ref "F") (pin "D1") (pinfunction "P_D1") (pintype "passive"))
    )
    (net (code "95") (name "/~{MQ0}") (class "Default")
      (node (ref "E2") (pin "66") (pinfunction "IO51_66") (pintype "bidirectional"))
      (node (ref "F") (pin "A2") (pinfunction "P_A2") (pintype "passive"))
    )
    (net (code "96") (name "/~{MQ10}") (class "Default")
      (node (ref "E2") (pin "67") (pinfunction "IO52_67") (pintype "bidirectional"))
      (node (ref "F") (pin "A1") (pinfunction "P_A1") (pintype "passive"))
    )
    (net (code "97") (name "/~{MQ11}") (class "Default")
      (node (ref "E2") (pin "65") (pinfunction "IO50_65") (pintype "bidirectional"))
      (node (ref "F") (pin "B1") (pinfunction "P_B1") (pintype "passive"))
    )
    (net (code "98") (name "/~{MQ_DATA}") (class "Default")
      (node (ref "E2") (pin "63") (pinfunction "IO49_63") (pintype "bidirectional"))
      (node (ref "F") (pin "B2") (pinfunction "P_B2") (pintype "passive"))
      (node (ref "R7") (pin "1") (pinfunction "1_1") (pintype "passive"))
    )
    (net (code "99") (name "/~{MQ_TO_BUS}") (class "Default")
      (node (ref "E2") (pin "35") (pinfunction "IO27_35") (pintype "bidirectional"))
      (node (ref "F") (pin "S2") (pinfunction "P_S2") (pintype "passive"))
    )
    (net (code "100") (name "/~{RIGHT}") (class "Default")
      (node (ref "E2") (pin "62") (pinfunction "IO48_62") (pintype "bidirectional"))
      (node (ref "F") (pin "C1") (pinfunction "P_C1") (pintype "passive"))
    )
    (net (code "101") (name "/~{SC_0}") (class "Default")
      (node (ref "E1") (pin "46") (pinfunction "IO34_46") (pintype "bidirectional"))
      (node (ref "E2") (pin "70") (pinfunction "IO54_70") (pintype "bidirectional"))
      (node (ref "H") (pin "U1") (pinfunction "P_U1") (pintype "passive"))
    )
    (net (code "102") (name "/~{SGT}") (class "Default")
      (node (ref "E1") (pin "66") (pinfunction "IO51_66") (pintype "bidirectional"))
      (node (ref "E2") (pin "86") (pinfunction "IO67_86") (pintype "bidirectional"))
      (node (ref "H") (pin "F1") (pinfunction "P_F1") (pintype "passive"))
      (node (ref "J") (pin "F1") (pinfunction "P_F1") (pintype "passive"))
    )
    (net (code "103") (name "/~{SHL_ENA}") (class "Default")
      (node (ref "E2") (pin "30") (pinfunction "IO22_30") (pintype "bidirectional"))
      (node (ref "F") (pin "V1") (pinfunction "P_V1") (pintype "passive"))
    )
    (net (code "104") (name "GND") (class "Default")
      (node (ref "C1") (pin "2") (pinfunction "2_2") (pintype "passive"))
      (node (ref "C2") (pin "2") (pinfunction "2_2") (pintype "passive"))
      (node (ref "C3") (pin "2") (pinfunction "2_2") (pintype "passive"))
      (node (ref "C33") (pin "-") (pinfunction "-_-") (pintype "passive"))
      (node (ref "C34") (pin "-") (pinfunction "-_-") (pintype "passive"))
      (node (ref "C35") (pin "-") (pinfunction "-_-") (pintype "passive"))
      (node (ref "C4") (pin "2") (pinfunction "2_2") (pintype "passive"))
      (node (ref "C5") (pin "2") (pinfunction "2_2") (pintype "passive"))
      (node (ref "C6") (pin "2") (pinfunction "2_2") (pintype "passive"))
      (node (ref "C7") (pin "2") (pinfunction "2_2") (pintype "passive"))
      (node (ref "C8") (pin "2") (pinfunction "2_2") (pintype "passive"))
      (node (ref "E1") (pin "29") (pinfunction "IO21_29") (pintype "bidirectional"))
      (node (ref "E1") (pin "37") (pinfunction "IO28_37") (pintype "bidirectional"))
      (node (ref "E1") (pin "62") (pinfunction "IO48_62") (pintype "bidirectional"))
      (node (ref "E1") (pin "85") (pinfunction "IO66_85") (pintype "bidirectional"))
      (node (ref "E2") (pin "27") (pinfunction "IO20_27") (pintype "bidirectional"))
      (node (ref "F") (pin "C2") (pinfunction "P_C2") (pintype "passive"))
      (node (ref "F") (pin "D2") (pinfunction "P_D2") (pintype "passive"))
      (node (ref "F") (pin "K1") (pinfunction "P_K1") (pintype "passive"))
      (node (ref "H") (pin "J2") (pinfunction "P_J2") (pintype "passive"))
      (node (ref "H") (pin "K2") (pinfunction "P_K2") (pintype "passive"))
      (node (ref "H") (pin "L2") (pinfunction "P_L2") (pintype "passive"))
      (node (ref "H") (pin "M2") (pinfunction "P_M2") (pintype "passive"))
      (node (ref "H") (pin "N2") (pinfunction "P_N2") (pintype "passive"))
      (node (ref "H") (pin "P2") (pinfunction "P_P2") (pintype "passive"))
      (node (ref "H") (pin "R2") (pinfunction "P_R2") (pintype "passive"))
      (node (ref "H") (pin "S2") (pinfunction "P_S2") (pintype "passive"))
      (node (ref "J") (pin "C1") (pinfunction "P_C1") (pintype "passive"))
      (node (ref "J") (pin "C2") (pinfunction "P_C2") (pintype "passive"))
      (node (ref "J") (pin "E1") (pinfunction "P_E1") (pintype "passive"))
      (node (ref "J") (pin "E2") (pinfunction "P_E2") (pintype "passive"))
      (node (ref "J") (pin "H1") (pinfunction "P_H1") (pintype "passive"))
      (node (ref "J") (pin "H2") (pinfunction "P_H2") (pintype "passive"))
      (node (ref "J") (pin "R1") (pinfunction "P_R1") (pintype "passive"))
      (node (ref "J") (pin "R2") (pinfunction "P_R2") (pintype "passive"))
      (node (ref "J") (pin "T1") (pinfunction "P_T1") (pintype "passive"))
      (node (ref "J") (pin "T2") (pinfunction "P_T2") (pintype "passive"))
      (node (ref "J") (pin "V1") (pinfunction "P_V1") (pintype "passive"))
      (node (ref "SV1") (pin "10") (pinfunction "10_10") (pintype "passive"))
      (node (ref "SV1") (pin "2") (pinfunction "2_2") (pintype "passive"))
      (node (ref "SV2") (pin "10") (pinfunction "10_10") (pintype "passive"))
      (node (ref "SV2") (pin "2") (pinfunction "2_2") (pintype "passive"))
      (node (ref "U$1") (pin "AC2") (pinfunction "1_AC2") (pintype "bidirectional"))
      (node (ref "U$1") (pin "AF1") (pinfunction "1_AF1") (pintype "bidirectional"))
      (node (ref "U$1") (pin "AF2") (pinfunction "1_AF2") (pintype "bidirectional"))
      (node (ref "U$1") (pin "AN1") (pinfunction "1_AN1") (pintype "bidirectional"))
      (node (ref "U$1") (pin "AN2") (pinfunction "1_AN2") (pintype "bidirectional"))
      (node (ref "U$1") (pin "AT1") (pinfunction "1_AT1") (pintype "bidirectional"))
      (node (ref "U$1") (pin "AT2") (pinfunction "1_AT2") (pintype "bidirectional"))
      (node (ref "U$1") (pin "BC1") (pinfunction "1_BC1") (pintype "bidirectional"))
      (node (ref "U$1") (pin "BC2") (pinfunction "1_BC2") (pintype "bidirectional"))
      (node (ref "U$1") (pin "BF1") (pinfunction "1_BF1") (pintype "bidirectional"))
      (node (ref "U$1") (pin "BF2") (pinfunction "1_BF2") (pintype "bidirectional"))
      (node (ref "U$1") (pin "BN1") (pinfunction "1_BN1") (pintype "bidirectional"))
      (node (ref "U$1") (pin "BT1") (pinfunction "1_BT1") (pintype "bidirectional"))
      (node (ref "U$1") (pin "CC1") (pinfunction "1_CC1") (pintype "bidirectional"))
      (node (ref "U$1") (pin "CC2") (pinfunction "1_CC2") (pintype "bidirectional"))
      (node (ref "U$1") (pin "CN1") (pinfunction "1_CN1") (pintype "bidirectional"))
      (node (ref "U$1") (pin "DC1") (pinfunction "1_DC1") (pintype "bidirectional"))
      (node (ref "U$1") (pin "DF1") (pinfunction "1_DF1") (pintype "bidirectional"))
      (node (ref "U$1") (pin "DN1") (pinfunction "1_DN1") (pintype "bidirectional"))
      (node (ref "U$1") (pin "DT1") (pinfunction "1_DT1") (pintype "bidirectional"))
    )
    (net (code "105") (name "VCC") (class "Default")
      (node (ref "C33") (pin "+") (pinfunction "+_+") (pintype "passive"))
      (node (ref "C34") (pin "+") (pinfunction "+_+") (pintype "passive"))
      (node (ref "C35") (pin "+") (pinfunction "+_+") (pintype "passive"))
      (node (ref "R1") (pin "2") (pinfunction "2_2") (pintype "passive"))
      (node (ref "R11") (pin "2") (pinfunction "2_2") (pintype "passive"))
      (node (ref "R12") (pin "2") (pinfunction "2_2") (pintype "passive"))
      (node (ref "R18") (pin "2") (pinfunction "2_2") (pintype "passive"))
      (node (ref "R2") (pin "2") (pinfunction "2_2") (pintype "passive"))
      (node (ref "R3") (pin "2") (pinfunction "2_2") (pintype "passive"))
      (node (ref "R4") (pin "2") (pinfunction "2_2") (pintype "passive"))
      (node (ref "R5") (pin "2") (pinfunction "2_2") (pintype "passive"))
      (node (ref "R6") (pin "2") (pinfunction "2_2") (pintype "passive"))
      (node (ref "R7") (pin "2") (pinfunction "2_2") (pintype "passive"))
      (node (ref "R8") (pin "2") (pinfunction "2_2") (pintype "passive"))
      (node (ref "R9") (pin "2") (pinfunction "2_2") (pintype "passive"))
      (node (ref "SV1") (pin "4") (pinfunction "4_4") (pintype "passive"))
      (node (ref "SV2") (pin "4") (pinfunction "4_4") (pintype "passive"))
      (node (ref "U$1") (pin "AA2") (pinfunction "1_AA2") (pintype "bidirectional"))
      (node (ref "U$1") (pin "BA2") (pinfunction "1_BA2") (pintype "bidirectional"))
      (node (ref "U$1") (pin "CA2") (pinfunction "1_CA2") (pintype "bidirectional"))
      (node (ref "VCCINT") (pin "1") (pinfunction "1_1") (pintype "bidirectional"))
      (node (ref "VCCIO") (pin "1") (pinfunction "1_1") (pintype "bidirectional"))
    )
    (net (code "106") (name "VCCINT") (class "Default")
      (node (ref "C1") (pin "1") (pinfunction "1_1") (pintype "passive"))
      (node (ref "C3") (pin "1") (pinfunction "1_1") (pintype "passive"))
      (node (ref "C6") (pin "1") (pinfunction "1_1") (pintype "passive"))
      (node (ref "C8") (pin "1") (pinfunction "1_1") (pintype "passive"))
      (node (ref "E1") (pin "42") (pinfunction "IO31_42") (pintype "bidirectional"))
      (node (ref "E1") (pin "87") (pinfunction "IO/GCLK3_87") (pintype "bidirectional"))
      (node (ref "E1") (pin "89") (pinfunction "IN/GCLK1_89") (pintype "input"))
      (node (ref "E1") (pin "90") (pinfunction "IN/OE1_90") (pintype "input"))
      (node (ref "E1") (pin "91") (pinfunction "IN/GCLR_91") (pintype "input"))
      (node (ref "E1") (pin "92") (pinfunction "IN/GCLK2/OE2_92") (pintype "input"))
      (node (ref "VCCINT") (pin "2") (pinfunction "2_2") (pintype "bidirectional"))
    )
    (net (code "107") (name "VCCIO") (class "Default")
      (node (ref "C2") (pin "1") (pinfunction "1_1") (pintype "passive"))
      (node (ref "C4") (pin "1") (pinfunction "1_1") (pintype "passive"))
      (node (ref "C5") (pin "1") (pinfunction "1_1") (pintype "passive"))
      (node (ref "C7") (pin "1") (pinfunction "1_1") (pintype "passive"))
      (node (ref "E1") (pin "21") (pinfunction "IO14_21") (pintype "bidirectional"))
      (node (ref "E1") (pin "54") (pinfunction "IO41_54") (pintype "bidirectional"))
      (node (ref "E1") (pin "83") (pinfunction "IO65_83") (pintype "bidirectional"))
      (node (ref "VCCIO") (pin "2") (pinfunction "2_2") (pintype "bidirectional"))
    )
    (net (code "108") (name "unconnected-(E1Q-IO8-Pad12)") (class "Default")
      (node (ref "E1") (pin "12") (pinfunction "IO8_12") (pintype "bidirectional"))
    )
    (net (code "109") (name "unconnected-(E1Q-IO35-Pad47)") (class "Default")
      (node (ref "E1") (pin "47") (pinfunction "IO35_47") (pintype "bidirectional"))
    )
    (net (code "110") (name "unconnected-(E1Q-IO39-Pad51)") (class "Default")
      (node (ref "E1") (pin "51") (pinfunction "IO39_51") (pintype "bidirectional"))
    )
    (net (code "111") (name "unconnected-(E1Q-IO61-Pad79)") (class "Default")
      (node (ref "E1") (pin "79") (pinfunction "IO61_79") (pintype "bidirectional"))
    )
    (net (code "112") (name "unconnected-(E1Q-IO62-Pad80)") (class "Default")
      (node (ref "E1") (pin "80") (pinfunction "IO62_80") (pintype "bidirectional"))
    )
    (net (code "113") (name "unconnected-(E1Q-IO63-Pad81)") (class "Default")
      (node (ref "E1") (pin "81") (pinfunction "IO63_81") (pintype "bidirectional"))
    )
    (net (code "114") (name "unconnected-(E1Q-IO64-Pad82)") (class "Default")
      (node (ref "E1") (pin "82") (pinfunction "IO64_82") (pintype "bidirectional"))
    )
    (net (code "115") (name "unconnected-(E1Q-IO67-Pad86)") (class "Default")
      (node (ref "E1") (pin "86") (pinfunction "IO67_86") (pintype "bidirectional"))
    )
    (net (code "116") (name "unconnected-(E1Q-IO69-Pad94)") (class "Default")
      (node (ref "E1") (pin "94") (pinfunction "IO69_94") (pintype "bidirectional"))
    )
    (net (code "117") (name "unconnected-(E1Q-IO70-Pad95)") (class "Default")
      (node (ref "E1") (pin "95") (pinfunction "IO70_95") (pintype "bidirectional"))
    )
    (net (code "118") (name "unconnected-(E1Q-IO71-Pad96)") (class "Default")
      (node (ref "E1") (pin "96") (pinfunction "IO71_96") (pintype "bidirectional"))
    )
    (net (code "119") (name "unconnected-(E1Q-IO72-Pad98)") (class "Default")
      (node (ref "E1") (pin "98") (pinfunction "IO72_98") (pintype "bidirectional"))
    )
    (net (code "120") (name "unconnected-(E2Q-IO8-Pad12)") (class "Default")
      (node (ref "E2") (pin "12") (pinfunction "IO8_12") (pintype "bidirectional"))
    )
    (net (code "121") (name "unconnected-(E2Q-IO19-Pad26)") (class "Default")
      (node (ref "E2") (pin "26") (pinfunction "IO19_26") (pintype "bidirectional"))
    )
    (net (code "122") (name "unconnected-(E2Q-IO33-Pad44)") (class "Default")
      (node (ref "E2") (pin "44") (pinfunction "IO33_44") (pintype "bidirectional"))
    )
    (net (code "123") (name "unconnected-(E2Q-IO45-Pad58)") (class "Default")
      (node (ref "E2") (pin "58") (pinfunction "IO45_58") (pintype "bidirectional"))
    )
    (net (code "124") (name "unconnected-(E2Q-IO53-Pad69)") (class "Default")
      (node (ref "E2") (pin "69") (pinfunction "IO53_69") (pintype "bidirectional"))
    )
    (net (code "125") (name "unconnected-(E2Q-IO75-Pad1)") (class "Default")
      (node (ref "E2") (pin "1") (pinfunction "IO75_1") (pintype "bidirectional"))
    )
    (net (code "126") (name "unconnected-(E2Q-IO{slash}GCLK3-Pad87)") (class "Default")
      (node (ref "E2") (pin "87") (pinfunction "IO/GCLK3_87") (pintype "bidirectional"))
    )
    (net (code "127") (name "unconnected-(E2Q-IO{slash}PD2-Pad43)") (class "Default")
      (node (ref "E2") (pin "43") (pinfunction "IO/PD2_43") (pintype "bidirectional"))
    )
    (net (code "128") (name "unconnected-(SV1-Pad6)") (class "Default")
      (node (ref "SV1") (pin "6") (pinfunction "6_6") (pintype "passive"))
    )
    (net (code "129") (name "unconnected-(SV1-Pad7)") (class "Default")
      (node (ref "SV1") (pin "7") (pinfunction "7_7") (pintype "passive"))
    )
    (net (code "130") (name "unconnected-(SV1-Pad8)") (class "Default")
      (node (ref "SV1") (pin "8") (pinfunction "8_8") (pintype "passive"))
    )
    (net (code "131") (name "unconnected-(SV2-Pad6)") (class "Default")
      (node (ref "SV2") (pin "6") (pinfunction "6_6") (pintype "passive"))
    )
    (net (code "132") (name "unconnected-(SV2-Pad7)") (class "Default")
      (node (ref "SV2") (pin "7") (pinfunction "7_7") (pintype "passive"))
    )
    (net (code "133") (name "unconnected-(SV2-Pad8)") (class "Default")
      (node (ref "SV2") (pin "8") (pinfunction "8_8") (pintype "passive"))
    )
  )
)
